# boardv2FNR.net
KiCad netlist of a schematic drawn in EAGLE
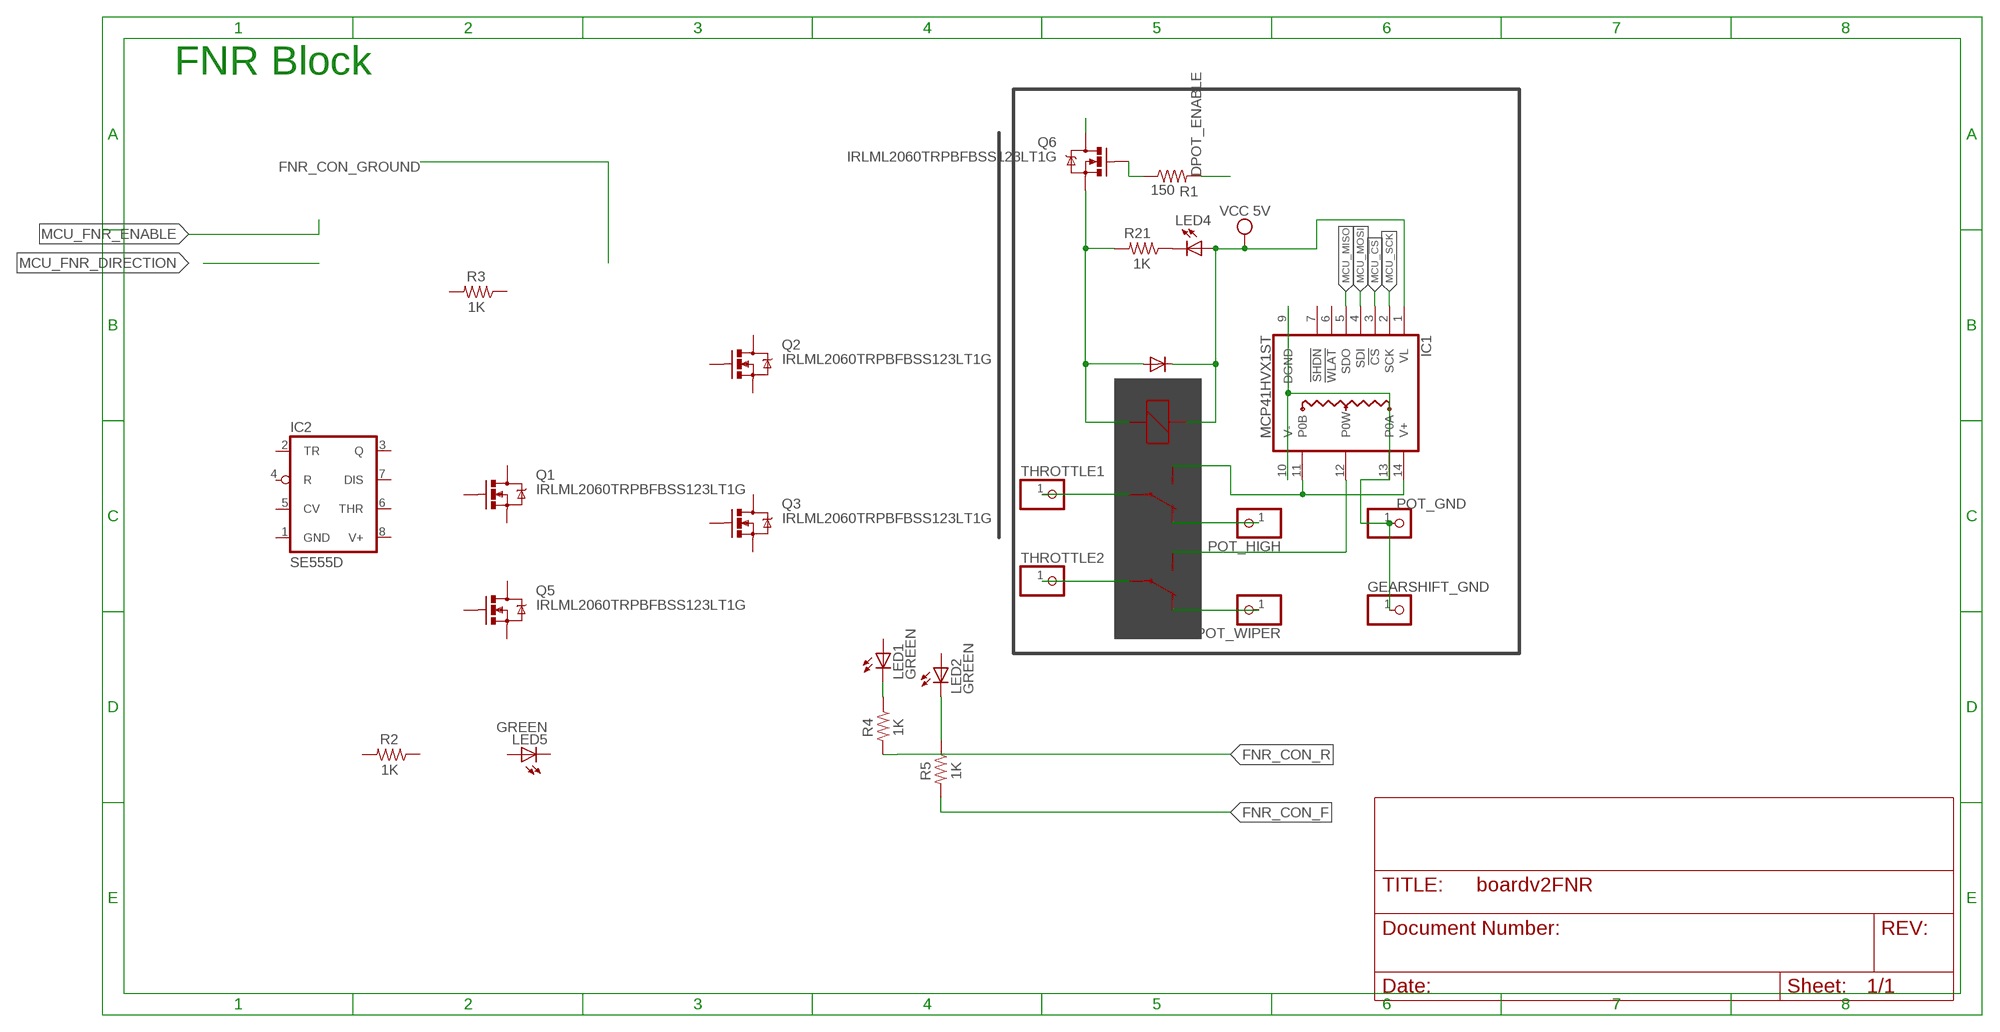
[diagram p0: schematic, sheet 1]

(export (version "E")
  (design (tool "Eeschema 10.0.6"))
  (components
    (comp (ref "D5")
      (value "1N4004")
      (footprint "eagle-import:DO41-10")
      (libsource (lib "eagle-import") (part "1N4004"))
    )
    (comp (ref "GEARSHIFT_GND")
      (value "PINHD-1X1")
      (footprint "eagle-import:1X01")
      (libsource (lib "eagle-import") (part "PINHD-1X1"))
    )
    (comp (ref "IC1")
      (value "MCP41HVX1ST")
      (footprint "eagle-import:TSSOP14")
      (libsource (lib "eagle-import") (part "MCP41HVX1ST"))
    )
    (comp (ref "IC2")
      (value "SE555D")
      (footprint "eagle-import:SO08")
      (libsource (lib "eagle-import") (part "555DSE"))
    )
    (comp (ref "K1")
      (value "G5V-2")
      (footprint "eagle-import:G5V-2")
      (fields (field (name "MPN") "G5V-2 5DC"))
      (libsource (lib "eagle-import") (part "G5V-2"))
    )
    (comp (ref "LED1")
      (value "GREEN")
      (footprint "eagle-import:LED3MM")
      (libsource (lib "eagle-import") (part "LED3MM"))
    )
    (comp (ref "LED2")
      (value "GREEN")
      (footprint "eagle-import:LED3MM")
      (libsource (lib "eagle-import") (part "LED3MM"))
    )
    (comp (ref "LED4")
      (value "LED3MM")
      (footprint "eagle-import:LED3MM")
      (libsource (lib "eagle-import") (part "LED3MM"))
    )
    (comp (ref "LED5")
      (value "GREEN")
      (footprint "eagle-import:LED3MM")
      (libsource (lib "eagle-import") (part "LED3MM"))
    )
    (comp (ref "POT_GND")
      (value "POT_GND")
      (footprint "eagle-import:1X01")
      (libsource (lib "eagle-import") (part "PINHD-1X1"))
    )
    (comp (ref "POT_HIGH")
      (value "PINHD-1X1")
      (footprint "eagle-import:1X01")
      (libsource (lib "eagle-import") (part "PINHD-1X1"))
    )
    (comp (ref "POT_WIPER")
      (value "PINHD-1X1")
      (footprint "eagle-import:1X01")
      (libsource (lib "eagle-import") (part "PINHD-1X1"))
    )
    (comp (ref "Q1")
      (value "IRLML2060TRPBFBSS123LT1G")
      (footprint "eagle-import:SOT23-3")
      (libsource (lib "eagle-import") (part "IRLML2060TRPBFBSS123LT1G"))
    )
    (comp (ref "Q2")
      (value "IRLML2060TRPBFBSS123LT1G")
      (footprint "eagle-import:SOT23-3")
      (libsource (lib "eagle-import") (part "IRLML2060TRPBFBSS123LT1G"))
    )
    (comp (ref "Q3")
      (value "IRLML2060TRPBFBSS123LT1G")
      (footprint "eagle-import:SOT23-3")
      (libsource (lib "eagle-import") (part "IRLML2060TRPBFBSS123LT1G"))
    )
    (comp (ref "Q5")
      (value "IRLML2060TRPBFBSS123LT1G")
      (footprint "eagle-import:SOT23-3")
      (libsource (lib "eagle-import") (part "IRLML2060TRPBFBSS123LT1G"))
    )
    (comp (ref "Q6")
      (value "IRLML2060TRPBFBSS123LT1G")
      (footprint "eagle-import:SOT23-3")
      (libsource (lib "eagle-import") (part "IRLML2060TRPBFBSS123LT1G"))
    )
    (comp (ref "R1")
      (value "150")
      (footprint "eagle-import:0204_5")
      (libsource (lib "eagle-import") (part "R-US_0204/5"))
    )
    (comp (ref "R2")
      (value "1K")
      (footprint "eagle-import:0204_5")
      (libsource (lib "eagle-import") (part "R-US_0204/5"))
    )
    (comp (ref "R3")
      (value "1K")
      (footprint "eagle-import:0204_5")
      (libsource (lib "eagle-import") (part "R-US_0204/5"))
    )
    (comp (ref "R4")
      (value "1K")
      (footprint "eagle-import:0204_5")
      (libsource (lib "eagle-import") (part "R-US_0204/5"))
    )
    (comp (ref "R5")
      (value "1K")
      (footprint "eagle-import:0204_5")
      (libsource (lib "eagle-import") (part "R-US_0204/5"))
    )
    (comp (ref "R21")
      (value "1K")
      (footprint "eagle-import:0204_5")
      (libsource (lib "eagle-import") (part "R-US_0204/5"))
    )
    (comp (ref "THROTTLE1")
      (value "PINHD-1X1")
      (footprint "eagle-import:1X01")
      (libsource (lib "eagle-import") (part "PINHD-1X1"))
    )
    (comp (ref "THROTTLE2")
      (value "PINHD-1X1")
      (footprint "eagle-import:1X01")
      (libsource (lib "eagle-import") (part "PINHD-1X1"))
    )
  )
  (nets
    (net (code "1") (name "/DPOT_ENABLE") (class "Default")
      (node (ref "R1") (pin "2") (pinfunction "2_2") (pintype "passive"))
    )
    (net (code "3") (name "/GND") (class "Default")
      (node (ref "IC2") (pin "1") (pinfunction "GND_1") (pintype "power_in"))
    )
    (net (code "4") (name "/MCU_~{CS}") (class "Default")
      (node (ref "IC1") (pin "3") (pinfunction "~{CS}_3") (pintype "bidirectional"))
    )
    (net (code "5") (name "/V+") (class "Default")
      (node (ref "IC2") (pin "8") (pinfunction "V+_8") (pintype "power_in"))
    )
    (net (code "6") (name "FNR_CON_F") (class "Default")
      (node (ref "R5") (pin "2") (pinfunction "2_2") (pintype "passive"))
    )
    (net (code "7") (name "FNR_CON_R") (class "Default")
      (node (ref "R4") (pin "2") (pinfunction "2_2") (pintype "passive"))
    )
    (net (code "10") (name "MCU_MISO") (class "Default")
      (node (ref "IC1") (pin "5") (pinfunction "SDO_5") (pintype "bidirectional"))
    )
    (net (code "11") (name "MCU_MOSI") (class "Default")
      (node (ref "IC1") (pin "4") (pinfunction "SDI_4") (pintype "bidirectional"))
    )
    (net (code "12") (name "MCU_SCK") (class "Default")
      (node (ref "IC1") (pin "2") (pinfunction "SCK_2") (pintype "bidirectional"))
    )
    (net (code "13") (name "Net-(IC1-DGND)") (class "Default")
      (node (ref "GEARSHIFT_GND") (pin "1") (pinfunction "1_1") (pintype "passive"))
      (node (ref "IC1") (pin "10") (pinfunction "V-_10") (pintype "power_in"))
      (node (ref "IC1") (pin "13") (pinfunction "P0A_13") (pintype "passive"))
      (node (ref "IC1") (pin "9") (pinfunction "DGND_9") (pintype "power_in"))
      (node (ref "POT_GND") (pin "1") (pinfunction "1_1") (pintype "passive"))
    )
    (net (code "14") (name "Net-(IC1-P0B)") (class "Default")
      (node (ref "IC1") (pin "11") (pinfunction "P0B_11") (pintype "passive"))
      (node (ref "IC1") (pin "14") (pinfunction "V+_14") (pintype "power_in"))
      (node (ref "K1") (pin "9") (pinfunction "S_9") (pintype "passive"))
    )
    (net (code "15") (name "Net-(IC1-P0W)") (class "Default")
      (node (ref "IC1") (pin "12") (pinfunction "P0W_12") (pintype "passive"))
      (node (ref "K1") (pin "8") (pinfunction "S_8") (pintype "passive"))
    )
    (net (code "16") (name "Net-(K1A-O)") (class "Default")
      (node (ref "K1") (pin "6") (pinfunction "O_6") (pintype "passive"))
      (node (ref "POT_WIPER") (pin "1") (pinfunction "1_1") (pintype "passive"))
    )
    (net (code "17") (name "Net-(K1A-P)") (class "Default")
      (node (ref "K1") (pin "4") (pinfunction "P_4") (pintype "passive"))
      (node (ref "THROTTLE2") (pin "1") (pinfunction "1_1") (pintype "passive"))
    )
    (net (code "18") (name "Net-(K1B-O)") (class "Default")
      (node (ref "K1") (pin "11") (pinfunction "O_11") (pintype "passive"))
      (node (ref "POT_HIGH") (pin "1") (pinfunction "1_1") (pintype "passive"))
    )
    (net (code "19") (name "Net-(K1B-P)") (class "Default")
      (node (ref "K1") (pin "13") (pinfunction "P_13") (pintype "passive"))
      (node (ref "THROTTLE1") (pin "1") (pinfunction "1_1") (pintype "passive"))
    )
    (net (code "20") (name "Net-(K1C-2)") (class "Default")
      (node (ref "D5") (pin "A") (pinfunction "A_A") (pintype "passive"))
      (node (ref "K1") (pin "16") (pinfunction "2_16") (pintype "passive"))
      (node (ref "Q6") (pin "2") (pinfunction "S_2") (pintype "passive"))
      (node (ref "R21") (pin "2") (pinfunction "2_2") (pintype "passive"))
    )
    (net (code "21") (name "Net-(LED1-C)") (class "Default")
      (node (ref "LED1") (pin "K") (pinfunction "C_K") (pintype "passive"))
      (node (ref "R4") (pin "1") (pinfunction "1_1") (pintype "passive"))
    )
    (net (code "22") (name "Net-(LED2-C)") (class "Default")
      (node (ref "LED2") (pin "K") (pinfunction "C_K") (pintype "passive"))
      (node (ref "R5") (pin "1") (pinfunction "1_1") (pintype "passive"))
    )
    (net (code "23") (name "Net-(LED4-C)") (class "Default")
      (node (ref "LED4") (pin "K") (pinfunction "C_K") (pintype "passive"))
      (node (ref "R21") (pin "1") (pinfunction "1_1") (pintype "passive"))
    )
    (net (code "24") (name "Net-(Q6-G)") (class "Default")
      (node (ref "Q6") (pin "1") (pinfunction "G_1") (pintype "passive"))
      (node (ref "R1") (pin "1") (pinfunction "1_1") (pintype "passive"))
    )
    (net (code "25") (name "VCC 5V") (class "Default")
      (node (ref "D5") (pin "C") (pinfunction "C_C") (pintype "passive"))
      (node (ref "IC1") (pin "1") (pinfunction "VL_1") (pintype "power_in"))
      (node (ref "K1") (pin "1") (pinfunction "1_1") (pintype "passive"))
      (node (ref "LED4") (pin "A") (pinfunction "A_A") (pintype "passive"))
    )
    (net (code "26") (name "unconnected-(IC1-~{SHDN}-Pad7)") (class "Default")
      (node (ref "IC1") (pin "7") (pinfunction "~{SHDN}_7") (pintype "bidirectional"))
    )
    (net (code "27") (name "unconnected-(IC1-~{WLAT}-Pad6)") (class "Default")
      (node (ref "IC1") (pin "6") (pinfunction "~{WLAT}_6") (pintype "bidirectional"))
    )
    (net (code "28") (name "unconnected-(IC2-CV-Pad5)") (class "Default")
      (node (ref "IC2") (pin "5") (pinfunction "CV_5") (pintype "input"))
    )
    (net (code "29") (name "unconnected-(IC2-DIS-Pad7)") (class "Default")
      (node (ref "IC2") (pin "7") (pinfunction "DIS_7") (pintype "input"))
    )
    (net (code "30") (name "unconnected-(IC2-Q-Pad3)") (class "Default")
      (node (ref "IC2") (pin "3") (pinfunction "Q_3") (pintype "output"))
    )
    (net (code "31") (name "unconnected-(IC2-R-Pad4)") (class "Default")
      (node (ref "IC2") (pin "4") (pinfunction "R_4") (pintype "input"))
    )
    (net (code "32") (name "unconnected-(IC2-THR-Pad6)") (class "Default")
      (node (ref "IC2") (pin "6") (pinfunction "THR_6") (pintype "input"))
    )
    (net (code "33") (name "unconnected-(IC2-TR-Pad2)") (class "Default")
      (node (ref "IC2") (pin "2") (pinfunction "TR_2") (pintype "input"))
    )
    (net (code "34") (name "unconnected-(LED1-PadA)") (class "Default")
      (node (ref "LED1") (pin "A") (pinfunction "A_A") (pintype "passive"))
    )
    (net (code "35") (name "unconnected-(LED2-PadA)") (class "Default")
      (node (ref "LED2") (pin "A") (pinfunction "A_A") (pintype "passive"))
    )
    (net (code "36") (name "unconnected-(LED5-C-PadK)") (class "Default")
      (node (ref "LED5") (pin "K") (pinfunction "C_K") (pintype "passive"))
    )
    (net (code "37") (name "unconnected-(LED5-PadA)") (class "Default")
      (node (ref "LED5") (pin "A") (pinfunction "A_A") (pintype "passive"))
    )
    (net (code "38") (name "unconnected-(Q1-D-Pad3)") (class "Default")
      (node (ref "Q1") (pin "3") (pinfunction "D_3") (pintype "passive"))
    )
    (net (code "39") (name "unconnected-(Q1-G-Pad1)") (class "Default")
      (node (ref "Q1") (pin "1") (pinfunction "G_1") (pintype "passive"))
    )
    (net (code "40") (name "unconnected-(Q1-S-Pad2)") (class "Default")
      (node (ref "Q1") (pin "2") (pinfunction "S_2") (pintype "passive"))
    )
    (net (code "41") (name "unconnected-(Q2-D-Pad3)") (class "Default")
      (node (ref "Q2") (pin "3") (pinfunction "D_3") (pintype "passive"))
    )
    (net (code "42") (name "unconnected-(Q2-G-Pad1)") (class "Default")
      (node (ref "Q2") (pin "1") (pinfunction "G_1") (pintype "passive"))
    )
    (net (code "43") (name "unconnected-(Q2-S-Pad2)") (class "Default")
      (node (ref "Q2") (pin "2") (pinfunction "S_2") (pintype "passive"))
    )
    (net (code "44") (name "unconnected-(Q3-D-Pad3)") (class "Default")
      (node (ref "Q3") (pin "3") (pinfunction "D_3") (pintype "passive"))
    )
    (net (code "45") (name "unconnected-(Q3-G-Pad1)") (class "Default")
      (node (ref "Q3") (pin "1") (pinfunction "G_1") (pintype "passive"))
    )
    (net (code "46") (name "unconnected-(Q3-S-Pad2)") (class "Default")
      (node (ref "Q3") (pin "2") (pinfunction "S_2") (pintype "passive"))
    )
    (net (code "47") (name "unconnected-(Q5-D-Pad3)") (class "Default")
      (node (ref "Q5") (pin "3") (pinfunction "D_3") (pintype "passive"))
    )
    (net (code "48") (name "unconnected-(Q5-G-Pad1)") (class "Default")
      (node (ref "Q5") (pin "1") (pinfunction "G_1") (pintype "passive"))
    )
    (net (code "49") (name "unconnected-(Q5-S-Pad2)") (class "Default")
      (node (ref "Q5") (pin "2") (pinfunction "S_2") (pintype "passive"))
    )
    (net (code "50") (name "unconnected-(Q6-D-Pad3)") (class "Default")
      (node (ref "Q6") (pin "3") (pinfunction "D_3") (pintype "passive"))
    )
    (net (code "51") (name "unconnected-(R2-Pad1)") (class "Default")
      (node (ref "R2") (pin "1") (pinfunction "1_1") (pintype "passive"))
    )
    (net (code "52") (name "unconnected-(R2-Pad2)") (class "Default")
      (node (ref "R2") (pin "2") (pinfunction "2_2") (pintype "passive"))
    )
    (net (code "53") (name "unconnected-(R3-Pad1)") (class "Default")
      (node (ref "R3") (pin "1") (pinfunction "1_1") (pintype "passive"))
    )
    (net (code "54") (name "unconnected-(R3-Pad2)") (class "Default")
      (node (ref "R3") (pin "2") (pinfunction "2_2") (pintype "passive"))
    )
  )
)
